# mrShark_12.net
KiCad netlist of a schematic drawn in EAGLE
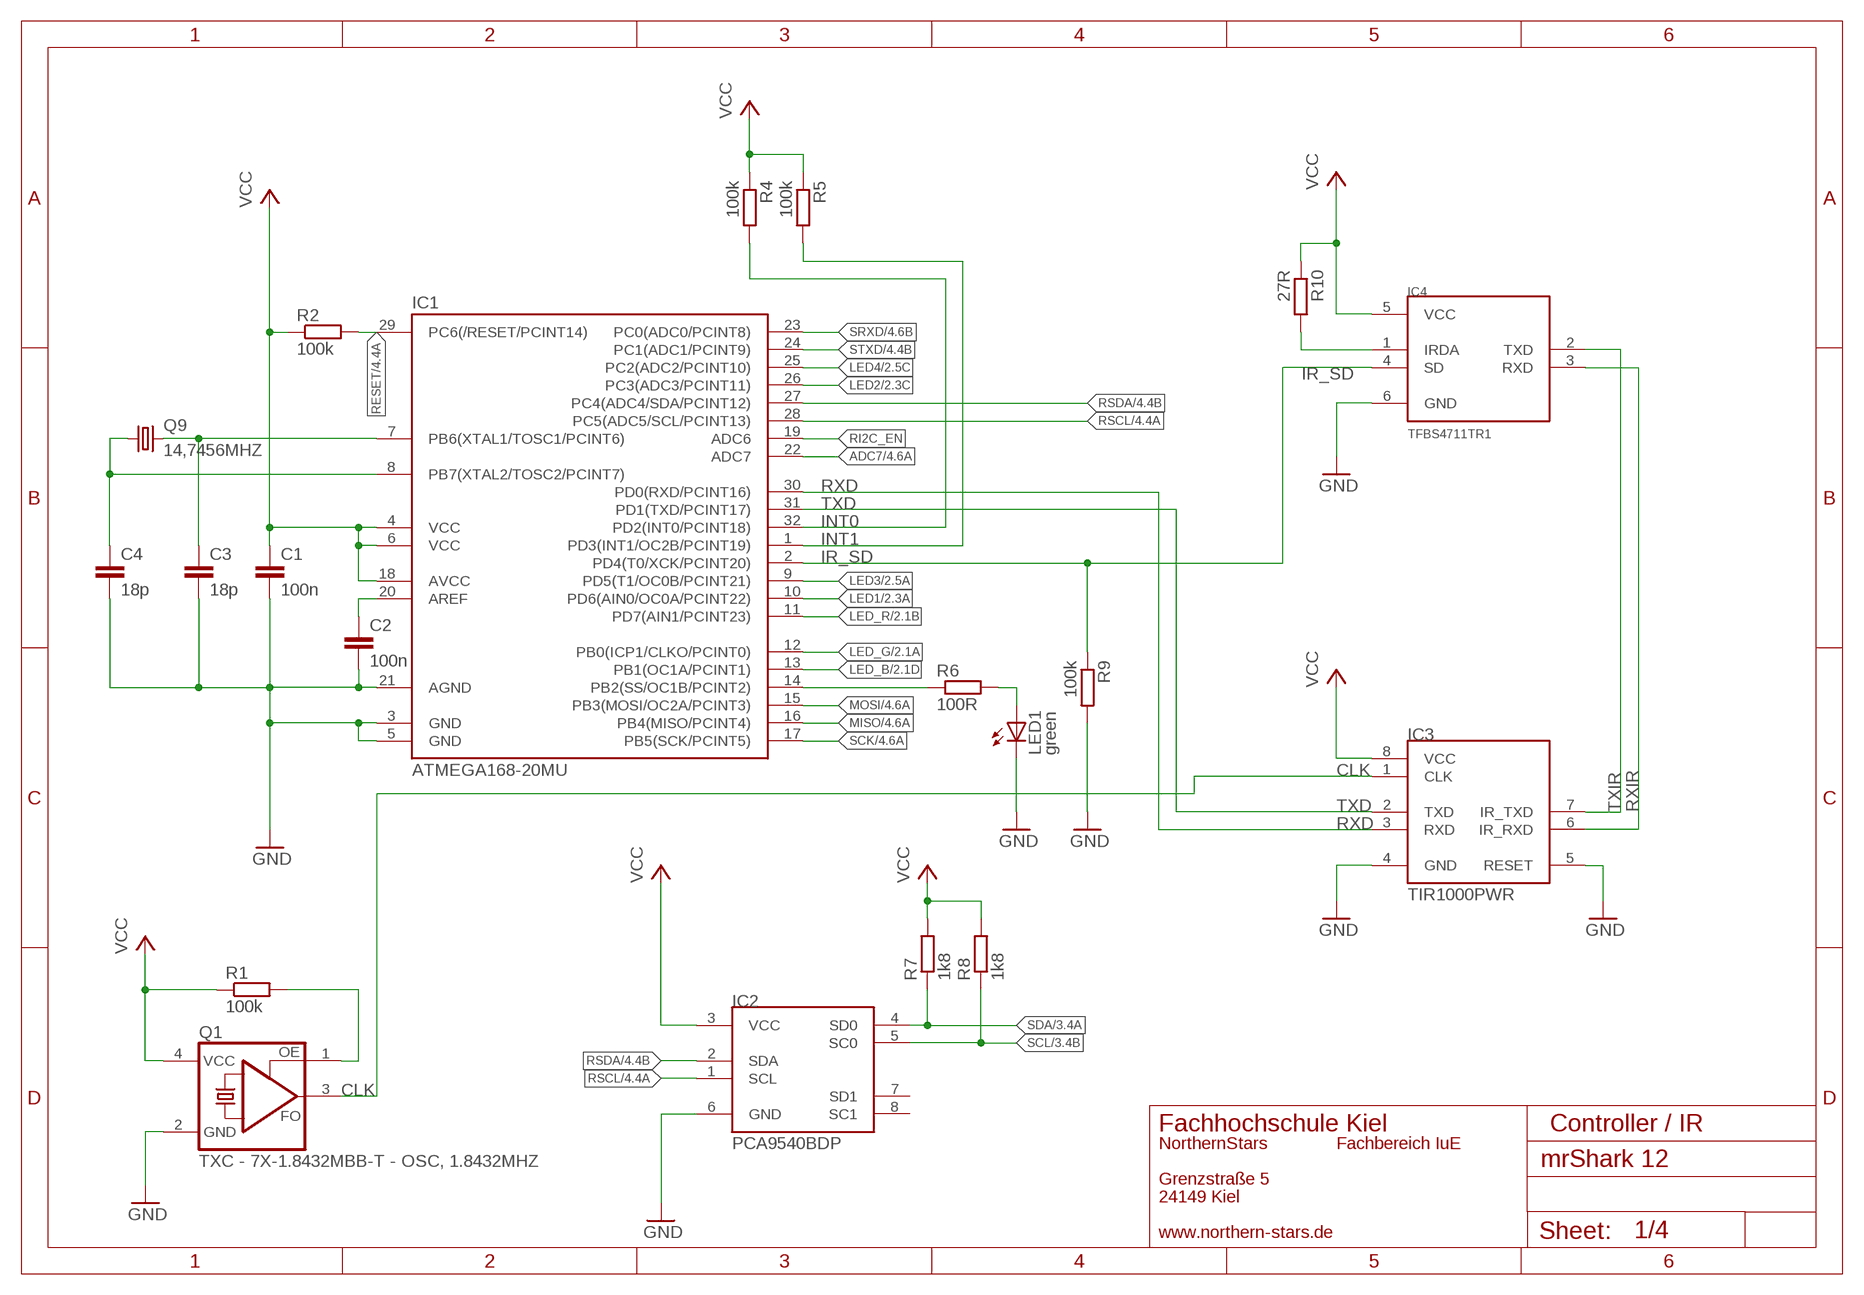
[diagram p0: schematic, sheet 1]
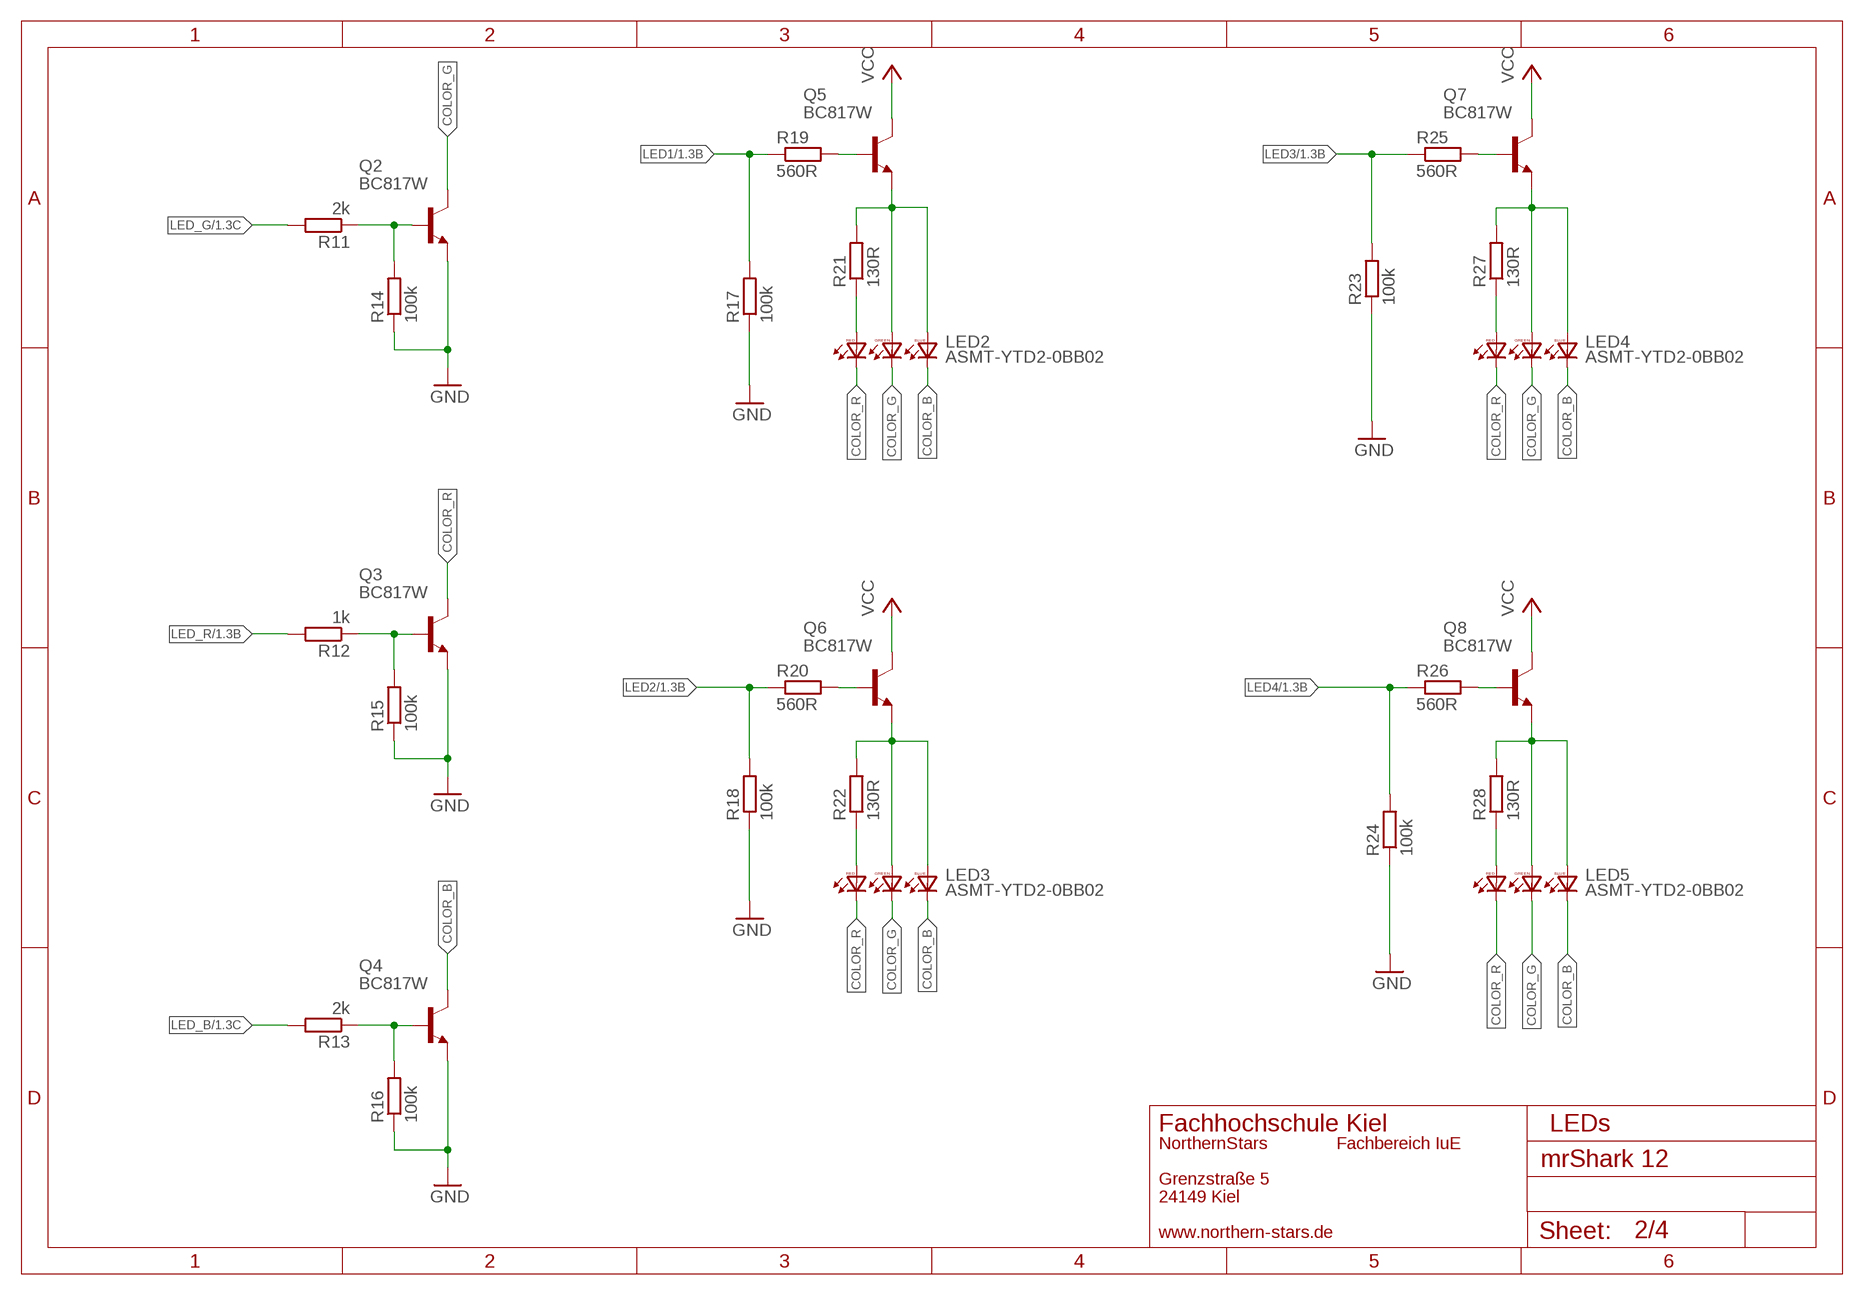
[diagram p1: schematic, sheet 2]
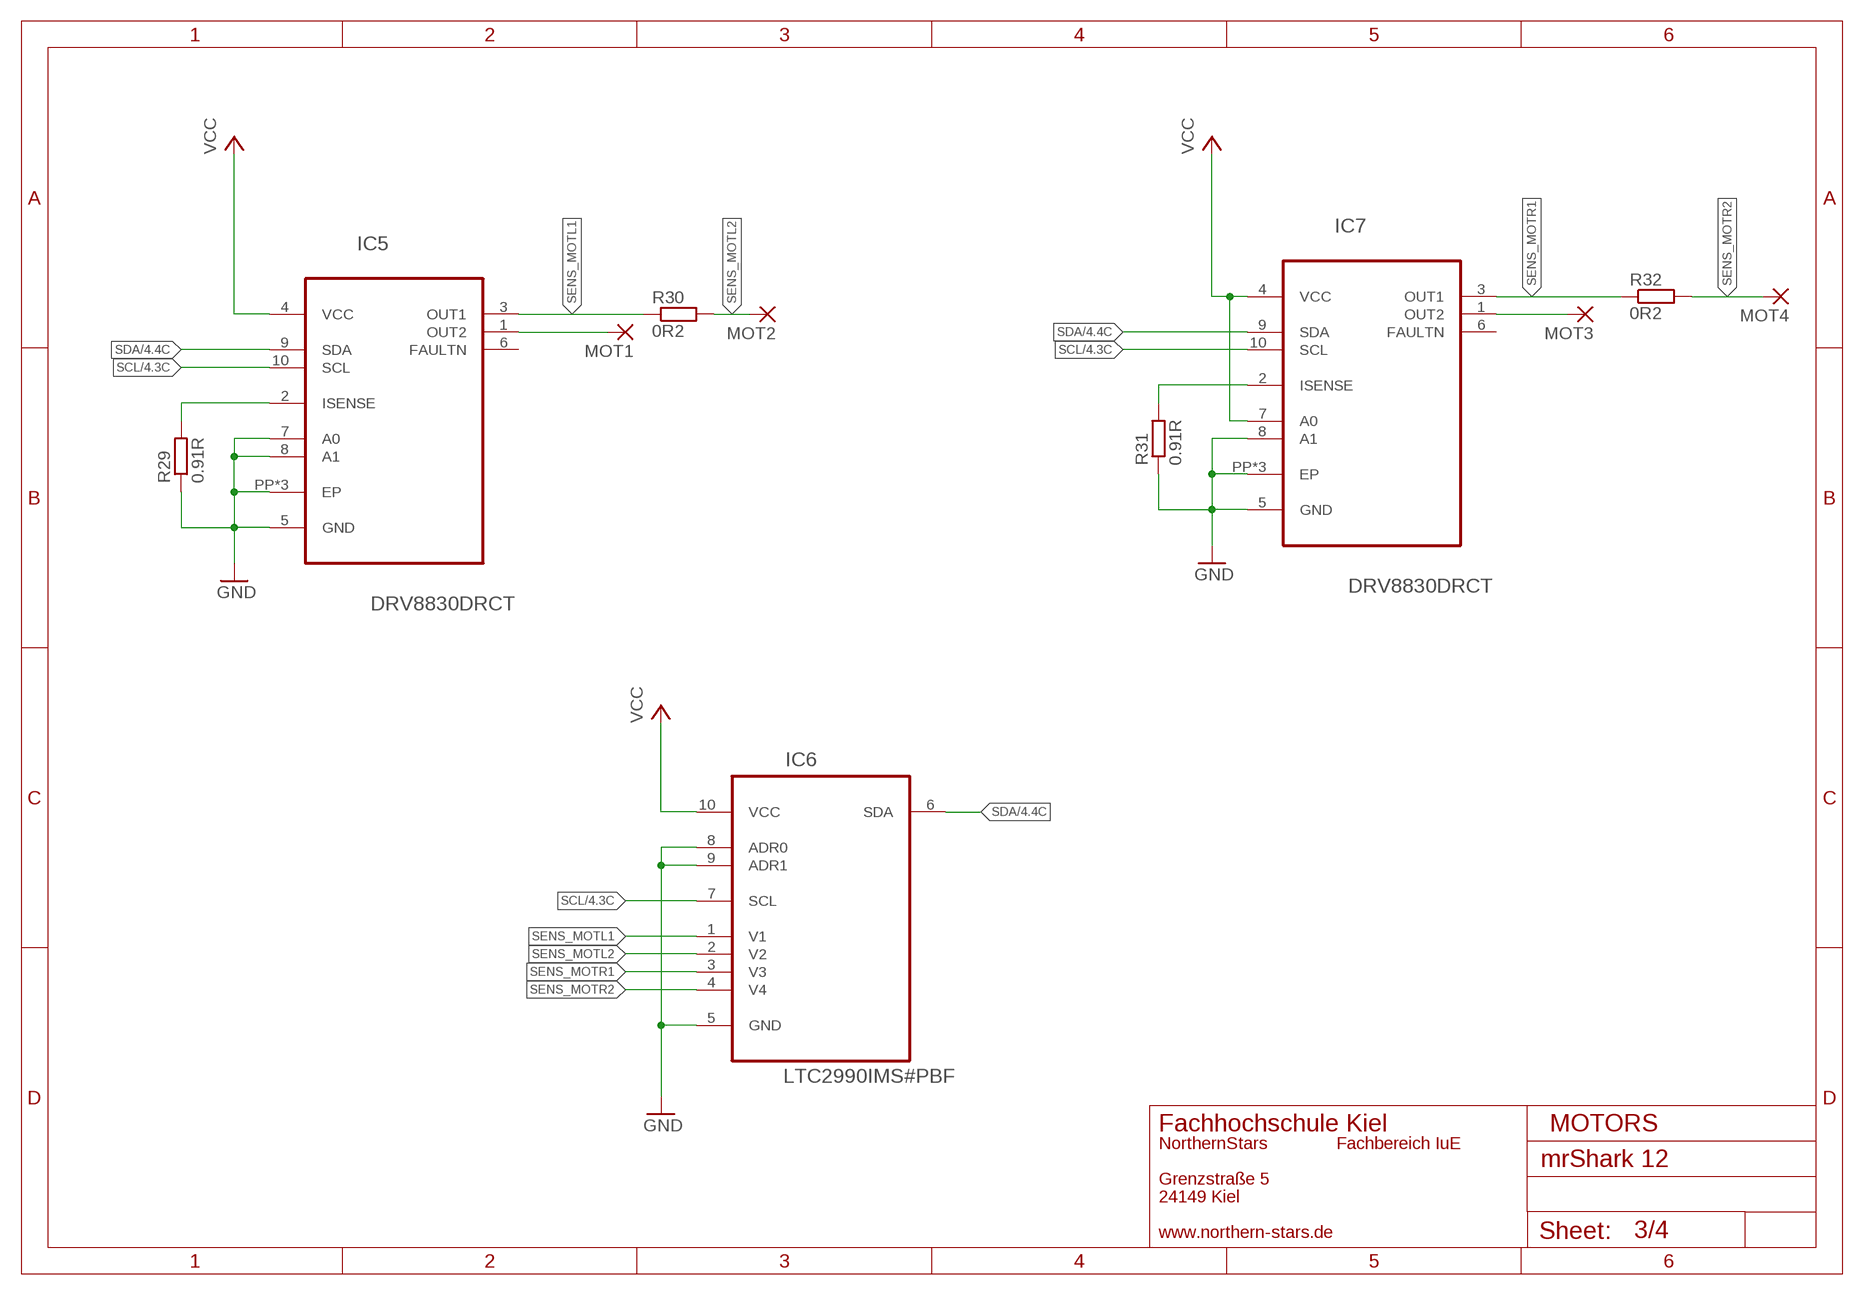
[diagram p2: schematic, sheet 3]
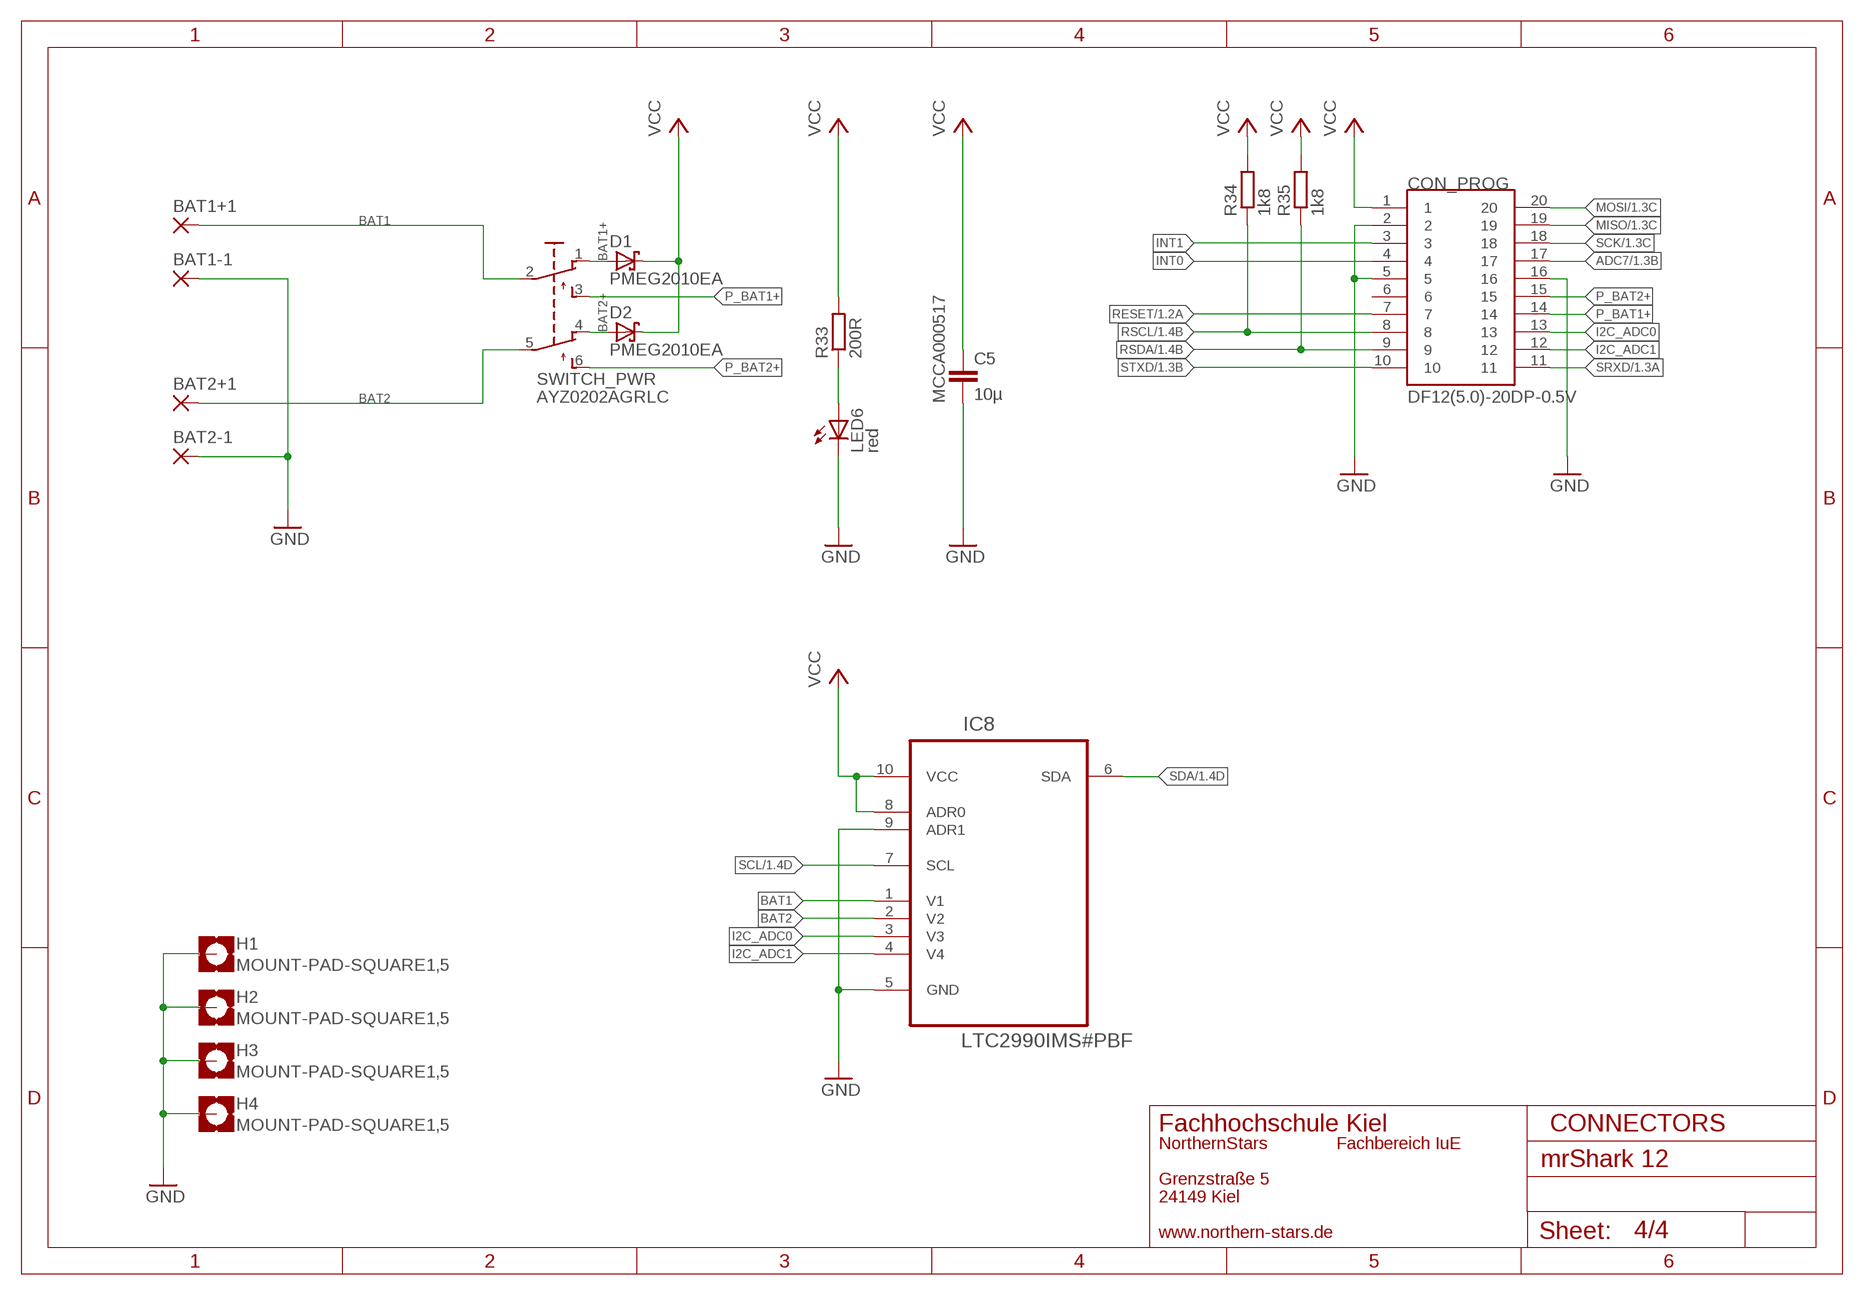
[diagram p3: schematic, sheet 4]

(export (version "E")
  (design (tool "Eeschema 10.0.6"))
  (components
    (comp (ref "C1")
      (value "100n")
      (footprint "eagle-import:C0201")
      (libsource (lib "eagle-import") (part "C-EUC0201"))
    )
    (comp (ref "C2")
      (value "100n")
      (footprint "eagle-import:C0201")
      (libsource (lib "eagle-import") (part "C-EUC0201"))
    )
    (comp (ref "C3")
      (value "18p")
      (footprint "eagle-import:C0201")
      (libsource (lib "eagle-import") (part "C-EUC0201"))
    )
    (comp (ref "C4")
      (value "18p")
      (footprint "eagle-import:C0201")
      (libsource (lib "eagle-import") (part "C-EUC0201"))
    )
    (comp (ref "IC1")
      (value "ATMEGA168-20MU")
      (footprint "eagle-import:MLF32")
      (libsource (lib "eagle-import") (part "ATMEGA48/88/168-MU"))
    )
    (comp (ref "IC2")
      (value "PCA9540BDP")
      (footprint "eagle-import:TSSOP8")
      (libsource (lib "eagle-import") (part "PCA9540TSSOP8"))
    )
    (comp (ref "IC3")
      (value "TIR1000PWR")
      (footprint "eagle-import:PW_R-PDSO-G08")
      (libsource (lib "eagle-import") (part "TIR1000PWR"))
    )
    (comp (ref "IC4")
      (value "TFBS4711TR1")
      (footprint "eagle-import:TFBS4711")
      (libsource (lib "eagle-import") (part "TFBS4711TR1"))
    )
    (comp (ref "LED1")
      (value "green")
      (footprint "eagle-import:CHIPLED_0603")
      (libsource (lib "eagle-import") (part "LEDCHIPLED_0603"))
    )
    (comp (ref "Q1")
      (value "TXC - 7X-1.8432MBB-T - OSC, 1.8432MHZ")
      (footprint "eagle-import:3.2X2.5")
      (libsource (lib "eagle-import") (part "7X-SERIES"))
    )
    (comp (ref "Q9")
      (value "14,7456MHZ")
      (footprint "eagle-import:TXC_7B_SERIES")
      (libsource (lib "eagle-import") (part "TXC-7B-SERIESSMD"))
    )
    (comp (ref "R1")
      (value "100k")
      (footprint "eagle-import:R0201")
      (libsource (lib "eagle-import") (part "R-EU_R0201"))
    )
    (comp (ref "R2")
      (value "100k")
      (footprint "eagle-import:R0201")
      (libsource (lib "eagle-import") (part "R-EU_R0201"))
    )
    (comp (ref "R4")
      (value "100k")
      (footprint "eagle-import:R0201")
      (libsource (lib "eagle-import") (part "R-EU_R0201"))
    )
    (comp (ref "R5")
      (value "100k")
      (footprint "eagle-import:R0201")
      (libsource (lib "eagle-import") (part "R-EU_R0201"))
    )
    (comp (ref "R6")
      (value "100R")
      (footprint "eagle-import:R0201")
      (libsource (lib "eagle-import") (part "R-EU_R0201"))
    )
    (comp (ref "R7")
      (value "1k8")
      (footprint "eagle-import:R0201")
      (libsource (lib "eagle-import") (part "R-EU_R0201"))
    )
    (comp (ref "R8")
      (value "1k8")
      (footprint "eagle-import:R0201")
      (libsource (lib "eagle-import") (part "R-EU_R0201"))
    )
    (comp (ref "R9")
      (value "100k")
      (footprint "eagle-import:R0201")
      (libsource (lib "eagle-import") (part "R-EU_R0201"))
    )
    (comp (ref "R10")
      (value "27R")
      (footprint "eagle-import:R0201")
      (libsource (lib "eagle-import") (part "R-EU_R0201"))
    )
    (comp (ref "BAT1+1")
      (value "1,6/0,9")
      (footprint "eagle-import:1,6_0,9")
      (libsource (lib "eagle-import") (part "1,6/0,9"))
    )
    (comp (ref "BAT1-1")
      (value "1,6/0,9")
      (footprint "eagle-import:1,6_0,9")
      (libsource (lib "eagle-import") (part "1,6/0,9"))
    )
    (comp (ref "BAT2+1")
      (value "1,6/0,9")
      (footprint "eagle-import:1,6_0,9")
      (libsource (lib "eagle-import") (part "1,6/0,9"))
    )
    (comp (ref "BAT2-1")
      (value "1,6/0,9")
      (footprint "eagle-import:1,6_0,9")
      (libsource (lib "eagle-import") (part "1,6/0,9"))
    )
    (comp (ref "C5")
      (value "10µ")
      (footprint "eagle-import:C0603K")
      (libsource (lib "eagle-import") (part "C-EUC0603K"))
    )
    (comp (ref "CON_PROG")
      (value "DF12(5.0)-20DP-0.5V")
      (footprint "eagle-import:DF12-20DP")
      (libsource (lib "eagle-import") (part "DF12-20DP"))
    )
    (comp (ref "D1")
      (value "PMEG2010EA")
      (footprint "eagle-import:SOD323-R")
      (libsource (lib "eagle-import") (part "PMEG2010EAR"))
    )
    (comp (ref "D2")
      (value "PMEG2010EA")
      (footprint "eagle-import:SOD323-R")
      (libsource (lib "eagle-import") (part "PMEG2010EAR"))
    )
    (comp (ref "H1")
      (value "MOUNT-PAD-SQUARE1,5")
      (footprint "eagle-import:0,75-PAD-SQUARE")
      (libsource (lib "eagle-import") (part "MOUNT-PAD-SQUARE1,5"))
    )
    (comp (ref "H2")
      (value "MOUNT-PAD-SQUARE1,5")
      (footprint "eagle-import:0,75-PAD-SQUARE")
      (libsource (lib "eagle-import") (part "MOUNT-PAD-SQUARE1,5"))
    )
    (comp (ref "H3")
      (value "MOUNT-PAD-SQUARE1,5")
      (footprint "eagle-import:0,75-PAD-SQUARE")
      (libsource (lib "eagle-import") (part "MOUNT-PAD-SQUARE1,5"))
    )
    (comp (ref "H4")
      (value "MOUNT-PAD-SQUARE1,5")
      (footprint "eagle-import:0,75-PAD-SQUARE")
      (libsource (lib "eagle-import") (part "MOUNT-PAD-SQUARE1,5"))
    )
    (comp (ref "IC8")
      (value "LTC2990IMS#PBF")
      (footprint "eagle-import:SOP50P490X110-10N")
      (libsource (lib "eagle-import") (part "LTC2990IMSPBF"))
    )
    (comp (ref "LED6")
      (value "red")
      (footprint "eagle-import:CHIPLED_0603")
      (libsource (lib "eagle-import") (part "LEDCHIPLED_0603"))
    )
    (comp (ref "R33")
      (value "200R")
      (footprint "eagle-import:R0201")
      (libsource (lib "eagle-import") (part "R-EU_R0201"))
    )
    (comp (ref "R34")
      (value "1k8")
      (footprint "eagle-import:R0201")
      (libsource (lib "eagle-import") (part "R-EU_R0201"))
    )
    (comp (ref "R35")
      (value "1k8")
      (footprint "eagle-import:R0201")
      (libsource (lib "eagle-import") (part "R-EU_R0201"))
    )
    (comp (ref "SWITCH_PWR")
      (value "AYZ0202AGRLC")
      (footprint "eagle-import:AYZ0202AGLRC")
      (libsource (lib "eagle-import") (part "AYZ0202AGRLC"))
    )
    (comp (ref "LED2")
      (value "ASMT-YTD2-0BB02")
      (footprint "eagle-import:PLCC6K")
      (libsource (lib "eagle-import") (part "PLCC6K"))
    )
    (comp (ref "LED3")
      (value "ASMT-YTD2-0BB02")
      (footprint "eagle-import:PLCC6K")
      (libsource (lib "eagle-import") (part "PLCC6K"))
    )
    (comp (ref "LED4")
      (value "ASMT-YTD2-0BB02")
      (footprint "eagle-import:PLCC6K")
      (libsource (lib "eagle-import") (part "PLCC6K"))
    )
    (comp (ref "LED5")
      (value "ASMT-YTD2-0BB02")
      (footprint "eagle-import:PLCC6K")
      (libsource (lib "eagle-import") (part "PLCC6K"))
    )
    (comp (ref "Q2")
      (value "BC817W")
      (footprint "eagle-import:SOT323-BEC")
      (libsource (lib "eagle-import") (part "BC817W"))
    )
    (comp (ref "Q3")
      (value "BC817W")
      (footprint "eagle-import:SOT323-BEC")
      (libsource (lib "eagle-import") (part "BC817W"))
    )
    (comp (ref "Q4")
      (value "BC817W")
      (footprint "eagle-import:SOT323-BEC")
      (libsource (lib "eagle-import") (part "BC817W"))
    )
    (comp (ref "Q5")
      (value "BC817W")
      (footprint "eagle-import:SOT323-BEC")
      (libsource (lib "eagle-import") (part "BC817W"))
    )
    (comp (ref "Q6")
      (value "BC817W")
      (footprint "eagle-import:SOT323-BEC")
      (libsource (lib "eagle-import") (part "BC817W"))
    )
    (comp (ref "Q7")
      (value "BC817W")
      (footprint "eagle-import:SOT323-BEC")
      (libsource (lib "eagle-import") (part "BC817W"))
    )
    (comp (ref "Q8")
      (value "BC817W")
      (footprint "eagle-import:SOT323-BEC")
      (libsource (lib "eagle-import") (part "BC817W"))
    )
    (comp (ref "R11")
      (value "2k")
      (footprint "eagle-import:R0201")
      (libsource (lib "eagle-import") (part "R-EU_R0201"))
    )
    (comp (ref "R12")
      (value "1k")
      (footprint "eagle-import:R0201")
      (libsource (lib "eagle-import") (part "R-EU_R0201"))
    )
    (comp (ref "R13")
      (value "2k")
      (footprint "eagle-import:R0201")
      (libsource (lib "eagle-import") (part "R-EU_R0201"))
    )
    (comp (ref "R14")
      (value "100k")
      (footprint "eagle-import:R0201")
      (libsource (lib "eagle-import") (part "R-EU_R0201"))
    )
    (comp (ref "R15")
      (value "100k")
      (footprint "eagle-import:R0201")
      (libsource (lib "eagle-import") (part "R-EU_R0201"))
    )
    (comp (ref "R16")
      (value "100k")
      (footprint "eagle-import:R0201")
      (libsource (lib "eagle-import") (part "R-EU_R0201"))
    )
    (comp (ref "R17")
      (value "100k")
      (footprint "eagle-import:R0201")
      (libsource (lib "eagle-import") (part "R-EU_R0201"))
    )
    (comp (ref "R18")
      (value "100k")
      (footprint "eagle-import:R0201")
      (libsource (lib "eagle-import") (part "R-EU_R0201"))
    )
    (comp (ref "R19")
      (value "560R")
      (footprint "eagle-import:R0201")
      (libsource (lib "eagle-import") (part "R-EU_R0201"))
    )
    (comp (ref "R20")
      (value "560R")
      (footprint "eagle-import:R0201")
      (libsource (lib "eagle-import") (part "R-EU_R0201"))
    )
    (comp (ref "R21")
      (value "130R")
      (footprint "eagle-import:R0201")
      (libsource (lib "eagle-import") (part "R-EU_R0201"))
    )
    (comp (ref "R22")
      (value "130R")
      (footprint "eagle-import:R0201")
      (libsource (lib "eagle-import") (part "R-EU_R0201"))
    )
    (comp (ref "R23")
      (value "100k")
      (footprint "eagle-import:R0201")
      (libsource (lib "eagle-import") (part "R-EU_R0201"))
    )
    (comp (ref "R24")
      (value "100k")
      (footprint "eagle-import:R0201")
      (libsource (lib "eagle-import") (part "R-EU_R0201"))
    )
    (comp (ref "R25")
      (value "560R")
      (footprint "eagle-import:R0201")
      (libsource (lib "eagle-import") (part "R-EU_R0201"))
    )
    (comp (ref "R26")
      (value "560R")
      (footprint "eagle-import:R0201")
      (libsource (lib "eagle-import") (part "R-EU_R0201"))
    )
    (comp (ref "R27")
      (value "130R")
      (footprint "eagle-import:R0201")
      (libsource (lib "eagle-import") (part "R-EU_R0201"))
    )
    (comp (ref "R28")
      (value "130R")
      (footprint "eagle-import:R0201")
      (libsource (lib "eagle-import") (part "R-EU_R0201"))
    )
    (comp (ref "IC5")
      (value "DRV8830DRCT")
      (footprint "eagle-import:S-PDSO-N10")
      (libsource (lib "eagle-import") (part "DRV8830DGQRWSON"))
    )
    (comp (ref "IC6")
      (value "LTC2990IMS#PBF")
      (footprint "eagle-import:SOP50P490X110-10N")
      (libsource (lib "eagle-import") (part "LTC2990IMSPBF"))
    )
    (comp (ref "IC7")
      (value "DRV8830DRCT")
      (footprint "eagle-import:S-PDSO-N10")
      (libsource (lib "eagle-import") (part "DRV8830DGQRWSON"))
    )
    (comp (ref "MOT1")
      (value "1,6/0,9")
      (footprint "eagle-import:1,6_0,9")
      (libsource (lib "eagle-import") (part "1,6/0,9"))
    )
    (comp (ref "MOT2")
      (value "1,6/0,9")
      (footprint "eagle-import:1,6_0,9")
      (libsource (lib "eagle-import") (part "1,6/0,9"))
    )
    (comp (ref "MOT3")
      (value "1,6/0,9")
      (footprint "eagle-import:1,6_0,9")
      (libsource (lib "eagle-import") (part "1,6/0,9"))
    )
    (comp (ref "MOT4")
      (value "1,6/0,9")
      (footprint "eagle-import:1,6_0,9")
      (libsource (lib "eagle-import") (part "1,6/0,9"))
    )
    (comp (ref "R29")
      (value "0.91R")
      (footprint "eagle-import:R0603")
      (libsource (lib "eagle-import") (part "R-EU_R0603"))
    )
    (comp (ref "R30")
      (value "0R2")
      (footprint "eagle-import:R0603")
      (libsource (lib "eagle-import") (part "R-EU_R0603"))
    )
    (comp (ref "R31")
      (value "0.91R")
      (footprint "eagle-import:R0603")
      (libsource (lib "eagle-import") (part "R-EU_R0603"))
    )
    (comp (ref "R32")
      (value "0R2")
      (footprint "eagle-import:R0603")
      (libsource (lib "eagle-import") (part "R-EU_R0603"))
    )
  )
  (nets
    (net (code "1") (name "ADC7") (class "Default")
      (node (ref "CON_PROG") (pin "17") (pinfunction "17_17") (pintype "bidirectional"))
      (node (ref "IC1") (pin "22") (pinfunction "ADC7_22") (pintype "passive"))
    )
    (net (code "2") (name "BAT1") (class "Default")
      (node (ref "BAT1+1") (pin "1") (pinfunction "P_1") (pintype "passive"))
      (node (ref "IC8") (pin "1") (pinfunction "V1_1") (pintype "input"))
      (node (ref "SWITCH_PWR") (pin "2") (pinfunction "P_2") (pintype "passive"))
    )
    (net (code "3") (name "BAT1+") (class "Default")
      (node (ref "D1") (pin "A") (pinfunction "A_A") (pintype "passive"))
      (node (ref "SWITCH_PWR") (pin "1") (pinfunction "O_1") (pintype "passive"))
    )
    (net (code "4") (name "BAT2") (class "Default")
      (node (ref "BAT2+1") (pin "1") (pinfunction "P_1") (pintype "passive"))
      (node (ref "IC8") (pin "2") (pinfunction "V2_2") (pintype "input"))
      (node (ref "SWITCH_PWR") (pin "5") (pinfunction "P1_5") (pintype "passive"))
    )
    (net (code "5") (name "BAT2+") (class "Default")
      (node (ref "D2") (pin "A") (pinfunction "A_A") (pintype "passive"))
      (node (ref "SWITCH_PWR") (pin "4") (pinfunction "O1_4") (pintype "passive"))
    )
    (net (code "6") (name "CLK") (class "Default")
      (node (ref "IC3") (pin "1") (pinfunction "CLK_1") (pintype "bidirectional"))
      (node (ref "Q1") (pin "3") (pinfunction "FO_3") (pintype "output"))
    )
    (net (code "7") (name "COLOR_B") (class "Default")
      (node (ref "LED2") (pin "1") (pinfunction "BC_1") (pintype "passive"))
      (node (ref "LED3") (pin "1") (pinfunction "BC_1") (pintype "passive"))
      (node (ref "LED4") (pin "1") (pinfunction "BC_1") (pintype "passive"))
      (node (ref "LED5") (pin "1") (pinfunction "BC_1") (pintype "passive"))
      (node (ref "Q4") (pin "C") (pinfunction "C_C") (pintype "passive"))
    )
    (net (code "8") (name "COLOR_G") (class "Default")
      (node (ref "LED2") (pin "2") (pinfunction "GC_2") (pintype "passive"))
      (node (ref "LED3") (pin "2") (pinfunction "GC_2") (pintype "passive"))
      (node (ref "LED4") (pin "2") (pinfunction "GC_2") (pintype "passive"))
      (node (ref "LED5") (pin "2") (pinfunction "GC_2") (pintype "passive"))
      (node (ref "Q2") (pin "C") (pinfunction "C_C") (pintype "passive"))
    )
    (net (code "9") (name "COLOR_R") (class "Default")
      (node (ref "LED2") (pin "3") (pinfunction "RC_3") (pintype "passive"))
      (node (ref "LED3") (pin "3") (pinfunction "RC_3") (pintype "passive"))
      (node (ref "LED4") (pin "3") (pinfunction "RC_3") (pintype "passive"))
      (node (ref "LED5") (pin "3") (pinfunction "RC_3") (pintype "passive"))
      (node (ref "Q3") (pin "C") (pinfunction "C_C") (pintype "passive"))
    )
    (net (code "10") (name "GND") (class "Default")
      (node (ref "BAT1-1") (pin "1") (pinfunction "P_1") (pintype "passive"))
      (node (ref "BAT2-1") (pin "1") (pinfunction "P_1") (pintype "passive"))
      (node (ref "C1") (pin "2") (pinfunction "2_2") (pintype "passive"))
      (node (ref "C2") (pin "2") (pinfunction "2_2") (pintype "passive"))
      (node (ref "C3") (pin "2") (pinfunction "2_2") (pintype "passive"))
      (node (ref "C4") (pin "2") (pinfunction "2_2") (pintype "passive"))
      (node (ref "C5") (pin "2") (pinfunction "2_2") (pintype "passive"))
      (node (ref "CON_PROG") (pin "16") (pinfunction "16_16") (pintype "bidirectional"))
      (node (ref "CON_PROG") (pin "2") (pinfunction "2_2") (pintype "bidirectional"))
      (node (ref "CON_PROG") (pin "5") (pinfunction "5_5") (pintype "bidirectional"))
      (node (ref "H1") (pin "P") (pinfunction "MOUNT_P") (pintype "passive"))
      (node (ref "H2") (pin "P") (pinfunction "MOUNT_P") (pintype "passive"))
      (node (ref "H3") (pin "P") (pinfunction "MOUNT_P") (pintype "passive"))
      (node (ref "H4") (pin "P") (pinfunction "MOUNT_P") (pintype "passive"))
      (node (ref "IC1") (pin "21") (pinfunction "AGND_21") (pintype "power_in"))
      (node (ref "IC1") (pin "3") (pinfunction "GND_3") (pintype "power_in"))
      (node (ref "IC1") (pin "5") (pinfunction "GND_5") (pintype "power_in"))
      (node (ref "IC2") (pin "6") (pinfunction "GND_6") (pintype "bidirectional"))
      (node (ref "IC3") (pin "4") (pinfunction "GND_4") (pintype "bidirectional"))
      (node (ref "IC3") (pin "5") (pinfunction "RESET_5") (pintype "bidirectional"))
      (node (ref "IC4") (pin "6") (pinfunction "GND_6") (pintype "bidirectional"))
      (node (ref "IC5") (pin "5") (pinfunction "GND_5") (pintype "passive"))
      (node (ref "IC5") (pin "7") (pinfunction "A0_7") (pintype "input"))
      (node (ref "IC5") (pin "8") (pinfunction "A1_8") (pintype "input"))
      (node (ref "IC5") (pin "PP") (pinfunction "EP_PP") (pintype "passive"))
      (node (ref "IC5") (pin "PP@1") (pinfunction "EP_PP@1") (pintype "passive"))
      (node (ref "IC5") (pin "PP@2") (pinfunction "EP_PP@2") (pintype "passive"))
      (node (ref "IC6") (pin "5") (pinfunction "GND_5") (pintype "passive"))
      (node (ref "IC6") (pin "8") (pinfunction "ADR0_8") (pintype "input"))
      (node (ref "IC6") (pin "9") (pinfunction "ADR1_9") (pintype "input"))
      (node (ref "IC7") (pin "5") (pinfunction "GND_5") (pintype "passive"))
      (node (ref "IC7") (pin "8") (pinfunction "A1_8") (pintype "input"))
      (node (ref "IC7") (pin "PP") (pinfunction "EP_PP") (pintype "passive"))
      (node (ref "IC7") (pin "PP@1") (pinfunction "EP_PP@1") (pintype "passive"))
      (node (ref "IC7") (pin "PP@2") (pinfunction "EP_PP@2") (pintype "passive"))
      (node (ref "IC8") (pin "5") (pinfunction "GND_5") (pintype "passive"))
      (node (ref "IC8") (pin "9") (pinfunction "ADR1_9") (pintype "input"))
      (node (ref "LED1") (pin "C") (pinfunction "C_C") (pintype "passive"))
      (node (ref "LED6") (pin "C") (pinfunction "C_C") (pintype "passive"))
      (node (ref "Q1") (pin "2") (pinfunction "GND_2") (pintype "power_in"))
      (node (ref "Q2") (pin "E") (pinfunction "E_E") (pintype "passive"))
      (node (ref "Q3") (pin "E") (pinfunction "E_E") (pintype "passive"))
      (node (ref "Q4") (pin "E") (pinfunction "E_E") (pintype "passive"))
      (node (ref "R14") (pin "1") (pinfunction "1_1") (pintype "passive"))
      (node (ref "R15") (pin "1") (pinfunction "1_1") (pintype "passive"))
      (node (ref "R16") (pin "1") (pinfunction "1_1") (pintype "passive"))
      (node (ref "R17") (pin "1") (pinfunction "1_1") (pintype "passive"))
      (node (ref "R18") (pin "1") (pinfunction "1_1") (pintype "passive"))
      (node (ref "R23") (pin "1") (pinfunction "1_1") (pintype "passive"))
      (node (ref "R24") (pin "1") (pinfunction "1_1") (pintype "passive"))
      (node (ref "R29") (pin "1") (pinfunction "1_1") (pintype "passive"))
      (node (ref "R31") (pin "1") (pinfunction "1_1") (pintype "passive"))
      (node (ref "R9") (pin "2") (pinfunction "2_2") (pintype "passive"))
    )
    (net (code "11") (name "I2C_ADC0") (class "Default")
      (node (ref "CON_PROG") (pin "13") (pinfunction "13_13") (pintype "bidirectional"))
      (node (ref "IC8") (pin "3") (pinfunction "V3_3") (pintype "input"))
    )
    (net (code "12") (name "I2C_ADC1") (class "Default")
      (node (ref "CON_PROG") (pin "12") (pinfunction "12_12") (pintype "bidirectional"))
      (node (ref "IC8") (pin "4") (pinfunction "V4_4") (pintype "input"))
    )
    (net (code "13") (name "INT0") (class "Default")
      (node (ref "CON_PROG") (pin "4") (pinfunction "4_4") (pintype "bidirectional"))
      (node (ref "IC1") (pin "32") (pinfunction "PD2(INT0/PCINT18)_32") (pintype "bidirectional"))
      (node (ref "R4") (pin "2") (pinfunction "2_2") (pintype "passive"))
    )
    (net (code "14") (name "INT1") (class "Default")
      (node (ref "CON_PROG") (pin "3") (pinfunction "3_3") (pintype "bidirectional"))
      (node (ref "IC1") (pin "1") (pinfunction "PD3(INT1/OC2B/PCINT19)_1") (pintype "bidirectional"))
      (node (ref "R5") (pin "2") (pinfunction "2_2") (pintype "passive"))
    )
    (net (code "15") (name "IR_SD") (class "Default")
      (node (ref "IC1") (pin "2") (pinfunction "PD4(T0/XCK/PCINT20)_2") (pintype "bidirectional"))
      (node (ref "IC4") (pin "4") (pinfunction "SD_4") (pintype "bidirectional"))
      (node (ref "R9") (pin "1") (pinfunction "1_1") (pintype "passive"))
    )
    (net (code "16") (name "LED1") (class "Default")
      (node (ref "IC1") (pin "10") (pinfunction "PD6(AIN0/OC0A/PCINT22)_10") (pintype "bidirectional"))
      (node (ref "R17") (pin "2") (pinfunction "2_2") (pintype "passive"))
      (node (ref "R19") (pin "1") (pinfunction "1_1") (pintype "passive"))
    )
    (net (code "17") (name "LED2") (class "Default")
      (node (ref "IC1") (pin "26") (pinfunction "PC3(ADC3/PCINT11)_26") (pintype "bidirectional"))
      (node (ref "R18") (pin "2") (pinfunction "2_2") (pintype "passive"))
      (node (ref "R20") (pin "1") (pinfunction "1_1") (pintype "passive"))
    )
    (net (code "18") (name "LED3") (class "Default")
      (node (ref "IC1") (pin "9") (pinfunction "PD5(T1/OC0B/PCINT21)_9") (pintype "bidirectional"))
      (node (ref "R23") (pin "2") (pinfunction "2_2") (pintype "passive"))
      (node (ref "R25") (pin "1") (pinfunction "1_1") (pintype "passive"))
    )
    (net (code "19") (name "LED4") (class "Default")
      (node (ref "IC1") (pin "25") (pinfunction "PC2(ADC2/PCINT10)_25") (pintype "bidirectional"))
      (node (ref "R24") (pin "2") (pinfunction "2_2") (pintype "passive"))
      (node (ref "R26") (pin "1") (pinfunction "1_1") (pintype "passive"))
    )
    (net (code "20") (name "LED_B") (class "Default")
      (node (ref "IC1") (pin "13") (pinfunction "PB1(OC1A/PCINT1)_13") (pintype "bidirectional"))
      (node (ref "R13") (pin "2") (pinfunction "2_2") (pintype "passive"))
    )
    (net (code "21") (name "LED_G") (class "Default")
      (node (ref "IC1") (pin "12") (pinfunction "PB0(ICP1/CLKO/PCINT0)_12") (pintype "bidirectional"))
      (node (ref "R11") (pin "2") (pinfunction "2_2") (pintype "passive"))
    )
    (net (code "22") (name "LED_R") (class "Default")
      (node (ref "IC1") (pin "11") (pinfunction "PD7(AIN1/PCINT23)_11") (pintype "bidirectional"))
      (node (ref "R12") (pin "2") (pinfunction "2_2") (pintype "passive"))
    )
    (net (code "23") (name "MISO") (class "Default")
      (node (ref "CON_PROG") (pin "19") (pinfunction "19_19") (pintype "bidirectional"))
      (node (ref "IC1") (pin "16") (pinfunction "PB4(MISO/PCINT4)_16") (pintype "bidirectional"))
    )
    (net (code "24") (name "MOSI") (class "Default")
      (node (ref "CON_PROG") (pin "20") (pinfunction "20_20") (pintype "bidirectional"))
      (node (ref "IC1") (pin "15") (pinfunction "PB3(MOSI/OC2A/PCINT3)_15") (pintype "bidirectional"))
    )
    (net (code "25") (name "Net-(IC1-AREF)") (class "Default")
      (node (ref "C2") (pin "1") (pinfunction "1_1") (pintype "passive"))
      (node (ref "IC1") (pin "20") (pinfunction "AREF_20") (pintype "passive"))
    )
    (net (code "26") (name "Net-(IC1-PB2(SS{slash}OC1B{slash}PCINT2))") (class "Default")
      (node (ref "IC1") (pin "14") (pinfunction "PB2(SS/OC1B/PCINT2)_14") (pintype "bidirectional"))
      (node (ref "R6") (pin "1") (pinfunction "1_1") (pintype "passive"))
    )
    (net (code "27") (name "Net-(IC1-PB6(XTAL1{slash}TOSC1{slash}PCINT6))") (class "Default")
      (node (ref "C3") (pin "1") (pinfunction "1_1") (pintype "passive"))
      (node (ref "IC1") (pin "7") (pinfunction "PB6(XTAL1/TOSC1/PCINT6)_7") (pintype "bidirectional"))
      (node (ref "Q9") (pin "3") (pinfunction "2_3") (pintype "passive"))
    )
    (net (code "28") (name "Net-(IC1-PB7(XTAL2{slash}TOSC2{slash}PCINT7))") (class "Default")
      (node (ref "C4") (pin "1") (pinfunction "1_1") (pintype "passive"))
      (node (ref "IC1") (pin "8") (pinfunction "PB7(XTAL2/TOSC2/PCINT7)_8") (pintype "bidirectional"))
      (node (ref "Q9") (pin "1") (pinfunction "1_1") (pintype "passive"))
    )
    (net (code "29") (name "Net-(IC4-IRDA)") (class "Default")
      (node (ref "IC4") (pin "1") (pinfunction "IRDA_1") (pintype "bidirectional"))
      (node (ref "R10") (pin "2") (pinfunction "2_2") (pintype "passive"))
    )
    (net (code "30") (name "Net-(IC5-ISENSE)") (class "Default")
      (node (ref "IC5") (pin "2") (pinfunction "ISENSE_2") (pintype "input"))
      (node (ref "R29") (pin "2") (pinfunction "2_2") (pintype "passive"))
    )
    (net (code "31") (name "Net-(IC5-OUT2)") (class "Default")
      (node (ref "IC5") (pin "1") (pinfunction "OUT2_1") (pintype "output"))
      (node (ref "MOT1") (pin "1") (pinfunction "P_1") (pintype "passive"))
    )
    (net (code "32") (name "Net-(IC7-ISENSE)") (class "Default")
      (node (ref "IC7") (pin "2") (pinfunction "ISENSE_2") (pintype "input"))
      (node (ref "R31") (pin "2") (pinfunction "2_2") (pintype "passive"))
    )
    (net (code "33") (name "Net-(IC7-OUT2)") (class "Default")
      (node (ref "IC7") (pin "1") (pinfunction "OUT2_1") (pintype "output"))
      (node (ref "MOT3") (pin "1") (pinfunction "P_1") (pintype "passive"))
    )
    (net (code "34") (name "Net-(LED1-PadA)") (class "Default")
      (node (ref "LED1") (pin "A") (pinfunction "A_A") (pintype "passive"))
      (node (ref "R6") (pin "2") (pinfunction "2_2") (pintype "passive"))
    )
    (net (code "35") (name "Net-(LED2-BA)") (class "Default")
      (node (ref "LED2") (pin "5") (pinfunction "GA_5") (pintype "passive"))
      (node (ref "LED2") (pin "6") (pinfunction "BA_6") (pintype "passive"))
      (node (ref "Q5") (pin "E") (pinfunction "E_E") (pintype "passive"))
      (node (ref "R21") (pin "2") (pinfunction "2_2") (pintype "passive"))
    )
    (net (code "36") (name "Net-(LED2-RA)") (class "Default")
      (node (ref "LED2") (pin "4") (pinfunction "RA_4") (pintype "passive"))
      (node (ref "R21") (pin "1") (pinfunction "1_1") (pintype "passive"))
    )
    (net (code "37") (name "Net-(LED3-BA)") (class "Default")
      (node (ref "LED3") (pin "5") (pinfunction "GA_5") (pintype "passive"))
      (node (ref "LED3") (pin "6") (pinfunction "BA_6") (pintype "passive"))
      (node (ref "Q6") (pin "E") (pinfunction "E_E") (pintype "passive"))
      (node (ref "R22") (pin "2") (pinfunction "2_2") (pintype "passive"))
    )
    (net (code "38") (name "Net-(LED3-RA)") (class "Default")
      (node (ref "LED3") (pin "4") (pinfunction "RA_4") (pintype "passive"))
      (node (ref "R22") (pin "1") (pinfunction "1_1") (pintype "passive"))
    )
    (net (code "39") (name "Net-(LED4-BA)") (class "Default")
      (node (ref "LED4") (pin "5") (pinfunction "GA_5") (pintype "passive"))
      (node (ref "LED4") (pin "6") (pinfunction "BA_6") (pintype "passive"))
      (node (ref "Q7") (pin "E") (pinfunction "E_E") (pintype "passive"))
      (node (ref "R27") (pin "2") (pinfunction "2_2") (pintype "passive"))
    )
    (net (code "40") (name "Net-(LED4-RA)") (class "Default")
      (node (ref "LED4") (pin "4") (pinfunction "RA_4") (pintype "passive"))
      (node (ref "R27") (pin "1") (pinfunction "1_1") (pintype "passive"))
    )
    (net (code "41") (name "Net-(LED5-BA)") (class "Default")
      (node (ref "LED5") (pin "5") (pinfunction "GA_5") (pintype "passive"))
      (node (ref "LED5") (pin "6") (pinfunction "BA_6") (pintype "passive"))
      (node (ref "Q8") (pin "E") (pinfunction "E_E") (pintype "passive"))
      (node (ref "R28") (pin "2") (pinfunction "2_2") (pintype "passive"))
    )
    (net (code "42") (name "Net-(LED5-RA)") (class "Default")
      (node (ref "LED5") (pin "4") (pinfunction "RA_4") (pintype "passive"))
      (node (ref "R28") (pin "1") (pinfunction "1_1") (pintype "passive"))
    )
    (net (code "43") (name "Net-(LED6-PadA)") (class "Default")
      (node (ref "LED6") (pin "A") (pinfunction "A_A") (pintype "passive"))
      (node (ref "R33") (pin "1") (pinfunction "1_1") (pintype "passive"))
    )
    (net (code "44") (name "Net-(Q1-OE)") (class "Default")
      (node (ref "Q1") (pin "1") (pinfunction "OE_1") (pintype "input"))
      (node (ref "R1") (pin "2") (pinfunction "2_2") (pintype "passive"))
    )
    (net (code "45") (name "Net-(Q2-PadB)") (class "Default")
      (node (ref "Q2") (pin "B") (pinfunction "B_B") (pintype "passive"))
      (node (ref "R11") (pin "1") (pinfunction "1_1") (pintype "passive"))
      (node (ref "R14") (pin "2") (pinfunction "2_2") (pintype "passive"))
    )
    (net (code "46") (name "Net-(Q3-PadB)") (class "Default")
      (node (ref "Q3") (pin "B") (pinfunction "B_B") (pintype "passive"))
      (node (ref "R12") (pin "1") (pinfunction "1_1") (pintype "passive"))
      (node (ref "R15") (pin "2") (pinfunction "2_2") (pintype "passive"))
    )
    (net (code "47") (name "Net-(Q4-PadB)") (class "Default")
      (node (ref "Q4") (pin "B") (pinfunction "B_B") (pintype "passive"))
      (node (ref "R13") (pin "1") (pinfunction "1_1") (pintype "passive"))
      (node (ref "R16") (pin "2") (pinfunction "2_2") (pintype "passive"))
    )
    (net (code "48") (name "Net-(Q5-PadB)") (class "Default")
      (node (ref "Q5") (pin "B") (pinfunction "B_B") (pintype "passive"))
      (node (ref "R19") (pin "2") (pinfunction "2_2") (pintype "passive"))
    )
    (net (code "49") (name "Net-(Q6-PadB)") (class "Default")
      (node (ref "Q6") (pin "B") (pinfunction "B_B") (pintype "passive"))
      (node (ref "R20") (pin "2") (pinfunction "2_2") (pintype "passive"))
    )
    (net (code "50") (name "Net-(Q7-PadB)") (class "Default")
      (node (ref "Q7") (pin "B") (pinfunction "B_B") (pintype "passive"))
      (node (ref "R25") (pin "2") (pinfunction "2_2") (pintype "passive"))
    )
    (net (code "51") (name "Net-(Q8-PadB)") (class "Default")
      (node (ref "Q8") (pin "B") (pinfunction "B_B") (pintype "passive"))
      (node (ref "R26") (pin "2") (pinfunction "2_2") (pintype "passive"))
    )
    (net (code "52") (name "P_BAT1+") (class "Default")
      (node (ref "CON_PROG") (pin "14") (pinfunction "14_14") (pintype "bidirectional"))
      (node (ref "SWITCH_PWR") (pin "3") (pinfunction "S_3") (pintype "passive"))
    )
    (net (code "53") (name "P_BAT2+") (class "Default")
      (node (ref "CON_PROG") (pin "15") (pinfunction "15_15") (pintype "bidirectional"))
      (node (ref "SWITCH_PWR") (pin "6") (pinfunction "S1_6") (pintype "passive"))
    )
    (net (code "54") (name "RESET") (class "Default")
      (node (ref "CON_PROG") (pin "7") (pinfunction "7_7") (pintype "bidirectional"))
      (node (ref "IC1") (pin "29") (pinfunction "PC6(/RESET/PCINT14)_29") (pintype "bidirectional"))
      (node (ref "R2") (pin "2") (pinfunction "2_2") (pintype "passive"))
    )
    (net (code "55") (name "RI2C_EN") (class "Default")
      (node (ref "IC1") (pin "19") (pinfunction "ADC6_19") (pintype "passive"))
    )
    (net (code "56") (name "RSCL") (class "Default")
      (node (ref "CON_PROG") (pin "8") (pinfunction "8_8") (pintype "bidirectional"))
      (node (ref "IC1") (pin "28") (pinfunction "PC5(ADC5/SCL/PCINT13)_28") (pintype "bidirectional"))
      (node (ref "IC2") (pin "1") (pinfunction "SCL_1") (pintype "bidirectional"))
      (node (ref "R34") (pin "1") (pinfunction "1_1") (pintype "passive"))
    )
    (net (code "57") (name "RSDA") (class "Default")
      (node (ref "CON_PROG") (pin "9") (pinfunction "9_9") (pintype "bidirectional"))
      (node (ref "IC1") (pin "27") (pinfunction "PC4(ADC4/SDA/PCINT12)_27") (pintype "bidirectional"))
      (node (ref "IC2") (pin "2") (pinfunction "SDA_2") (pintype "bidirectional"))
      (node (ref "R35") (pin "1") (pinfunction "1_1") (pintype "passive"))
    )
    (net (code "58") (name "RXD") (class "Default")
      (node (ref "IC1") (pin "30") (pinfunction "PD0(RXD/PCINT16)_30") (pintype "bidirectional"))
      (node (ref "IC3") (pin "3") (pinfunction "RXD_3") (pintype "bidirectional"))
    )
    (net (code "59") (name "RXIR") (class "Default")
      (node (ref "IC3") (pin "6") (pinfunction "IR_RXD_6") (pintype "bidirectional"))
      (node (ref "IC4") (pin "3") (pinfunction "RXD_3") (pintype "output"))
    )
    (net (code "60") (name "SCK") (class "Default")
      (node (ref "CON_PROG") (pin "18") (pinfunction "18_18") (pintype "bidirectional"))
      (node (ref "IC1") (pin "17") (pinfunction "PB5(SCK/PCINT5)_17") (pintype "bidirectional"))
    )
    (net (code "61") (name "SCL") (class "Default")
      (node (ref "IC2") (pin "5") (pinfunction "SC0_5") (pintype "bidirectional"))
      (node (ref "IC5") (pin "10") (pinfunction "SCL_10") (pintype "input"))
      (node (ref "IC6") (pin "7") (pinfunction "SCL_7") (pintype "input"))
      (node (ref "IC7") (pin "10") (pinfunction "SCL_10") (pintype "input"))
      (node (ref "IC8") (pin "7") (pinfunction "SCL_7") (pintype "input"))
      (node (ref "R8") (pin "1") (pinfunction "1_1") (pintype "passive"))
    )
    (net (code "62") (name "SDA") (class "Default")
      (node (ref "IC2") (pin "4") (pinfunction "SD0_4") (pintype "bidirectional"))
      (node (ref "IC5") (pin "9") (pinfunction "SDA_9") (pintype "bidirectional"))
      (node (ref "IC6") (pin "6") (pinfunction "SDA_6") (pintype "bidirectional"))
      (node (ref "IC7") (pin "9") (pinfunction "SDA_9") (pintype "bidirectional"))
      (node (ref "IC8") (pin "6") (pinfunction "SDA_6") (pintype "bidirectional"))
      (node (ref "R7") (pin "1") (pinfunction "1_1") (pintype "passive"))
    )
    (net (code "63") (name "SENS_MOTL1") (class "Default")
      (node (ref "IC5") (pin "3") (pinfunction "OUT1_3") (pintype "output"))
      (node (ref "IC6") (pin "1") (pinfunction "V1_1") (pintype "input"))
      (node (ref "R30") (pin "1") (pinfunction "1_1") (pintype "passive"))
    )
    (net (code "64") (name "SENS_MOTL2") (class "Default")
      (node (ref "IC6") (pin "2") (pinfunction "V2_2") (pintype "input"))
      (node (ref "MOT2") (pin "1") (pinfunction "P_1") (pintype "passive"))
      (node (ref "R30") (pin "2") (pinfunction "2_2") (pintype "passive"))
    )
    (net (code "65") (name "SENS_MOTR1") (class "Default")
      (node (ref "IC6") (pin "3") (pinfunction "V3_3") (pintype "input"))
      (node (ref "IC7") (pin "3") (pinfunction "OUT1_3") (pintype "output"))
      (node (ref "R32") (pin "1") (pinfunction "1_1") (pintype "passive"))
    )
    (net (code "66") (name "SENS_MOTR2") (class "Default")
      (node (ref "IC6") (pin "4") (pinfunction "V4_4") (pintype "input"))
      (node (ref "MOT4") (pin "1") (pinfunction "P_1") (pintype "passive"))
      (node (ref "R32") (pin "2") (pinfunction "2_2") (pintype "passive"))
    )
    (net (code "67") (name "SRXD") (class "Default")
      (node (ref "CON_PROG") (pin "11") (pinfunction "11_11") (pintype "bidirectional"))
      (node (ref "IC1") (pin "23") (pinfunction "PC0(ADC0/PCINT8)_23") (pintype "bidirectional"))
    )
    (net (code "68") (name "STXD") (class "Default")
      (node (ref "CON_PROG") (pin "10") (pinfunction "10_10") (pintype "bidirectional"))
      (node (ref "IC1") (pin "24") (pinfunction "PC1(ADC1/PCINT9)_24") (pintype "bidirectional"))
    )
    (net (code "69") (name "TXD") (class "Default")
      (node (ref "IC1") (pin "31") (pinfunction "PD1(TXD/PCINT17)_31") (pintype "bidirectional"))
      (node (ref "IC3") (pin "2") (pinfunction "TXD_2") (pintype "bidirectional"))
    )
    (net (code "70") (name "TXIR") (class "Default")
      (node (ref "IC3") (pin "7") (pinfunction "IR_TXD_7") (pintype "bidirectional"))
      (node (ref "IC4") (pin "2") (pinfunction "TXD_2") (pintype "input"))
    )
    (net (code "71") (name "VCC") (class "Default")
      (node (ref "C1") (pin "1") (pinfunction "1_1") (pintype "passive"))
      (node (ref "C5") (pin "1") (pinfunction "1_1") (pintype "passive"))
      (node (ref "CON_PROG") (pin "1") (pinfunction "1_1") (pintype "bidirectional"))
      (node (ref "D1") (pin "C") (pinfunction "C_C") (pintype "passive"))
      (node (ref "D2") (pin "C") (pinfunction "C_C") (pintype "passive"))
      (node (ref "IC1") (pin "18") (pinfunction "AVCC_18") (pintype "passive"))
      (node (ref "IC1") (pin "4") (pinfunction "VCC_4") (pintype "power_in"))
      (node (ref "IC1") (pin "6") (pinfunction "VCC_6") (pintype "power_in"))
      (node (ref "IC2") (pin "3") (pinfunction "VCC_3") (pintype "bidirectional"))
      (node (ref "IC3") (pin "8") (pinfunction "VCC_8") (pintype "bidirectional"))
      (node (ref "IC4") (pin "5") (pinfunction "VCC_5") (pintype "power_in"))
      (node (ref "IC5") (pin "4") (pinfunction "VCC_4") (pintype "power_in"))
      (node (ref "IC6") (pin "10") (pinfunction "VCC_10") (pintype "power_in"))
      (node (ref "IC7") (pin "4") (pinfunction "VCC_4") (pintype "power_in"))
      (node (ref "IC7") (pin "7") (pinfunction "A0_7") (pintype "input"))
      (node (ref "IC8") (pin "10") (pinfunction "VCC_10") (pintype "power_in"))
      (node (ref "IC8") (pin "8") (pinfunction "ADR0_8") (pintype "input"))
      (node (ref "Q1") (pin "4") (pinfunction "VCC_4") (pintype "power_in"))
      (node (ref "Q5") (pin "C") (pinfunction "C_C") (pintype "passive"))
      (node (ref "Q6") (pin "C") (pinfunction "C_C") (pintype "passive"))
      (node (ref "Q7") (pin "C") (pinfunction "C_C") (pintype "passive"))
      (node (ref "Q8") (pin "C") (pinfunction "C_C") (pintype "passive"))
      (node (ref "R1") (pin "1") (pinfunction "1_1") (pintype "passive"))
      (node (ref "R10") (pin "1") (pinfunction "1_1") (pintype "passive"))
      (node (ref "R2") (pin "1") (pinfunction "1_1") (pintype "passive"))
      (node (ref "R33") (pin "2") (pinfunction "2_2") (pintype "passive"))
      (node (ref "R34") (pin "2") (pinfunction "2_2") (pintype "passive"))
      (node (ref "R35") (pin "2") (pinfunction "2_2") (pintype "passive"))
      (node (ref "R4") (pin "1") (pinfunction "1_1") (pintype "passive"))
      (node (ref "R5") (pin "1") (pinfunction "1_1") (pintype "passive"))
      (node (ref "R7") (pin "2") (pinfunction "2_2") (pintype "passive"))
      (node (ref "R8") (pin "2") (pinfunction "2_2") (pintype "passive"))
    )
    (net (code "72") (name "unconnected-(CON_PROG-Pad6)") (class "Default")
      (node (ref "CON_PROG") (pin "6") (pinfunction "6_6") (pintype "bidirectional"))
    )
    (net (code "73") (name "unconnected-(IC2-SC1-Pad8)") (class "Default")
      (node (ref "IC2") (pin "8") (pinfunction "SC1_8") (pintype "bidirectional"))
    )
    (net (code "74") (name "unconnected-(IC2-SD1-Pad7)") (class "Default")
      (node (ref "IC2") (pin "7") (pinfunction "SD1_7") (pintype "bidirectional"))
    )
    (net (code "75") (name "unconnected-(IC5-FAULTN-Pad6)") (class "Default")
      (node (ref "IC5") (pin "6") (pinfunction "FAULTN_6") (pintype "output"))
    )
    (net (code "76") (name "unconnected-(IC7-FAULTN-Pad6)") (class "Default")
      (node (ref "IC7") (pin "6") (pinfunction "FAULTN_6") (pintype "output"))
    )
  )
)
